# Motor.net
KiCad netlist of a schematic drawn in Altium Designer
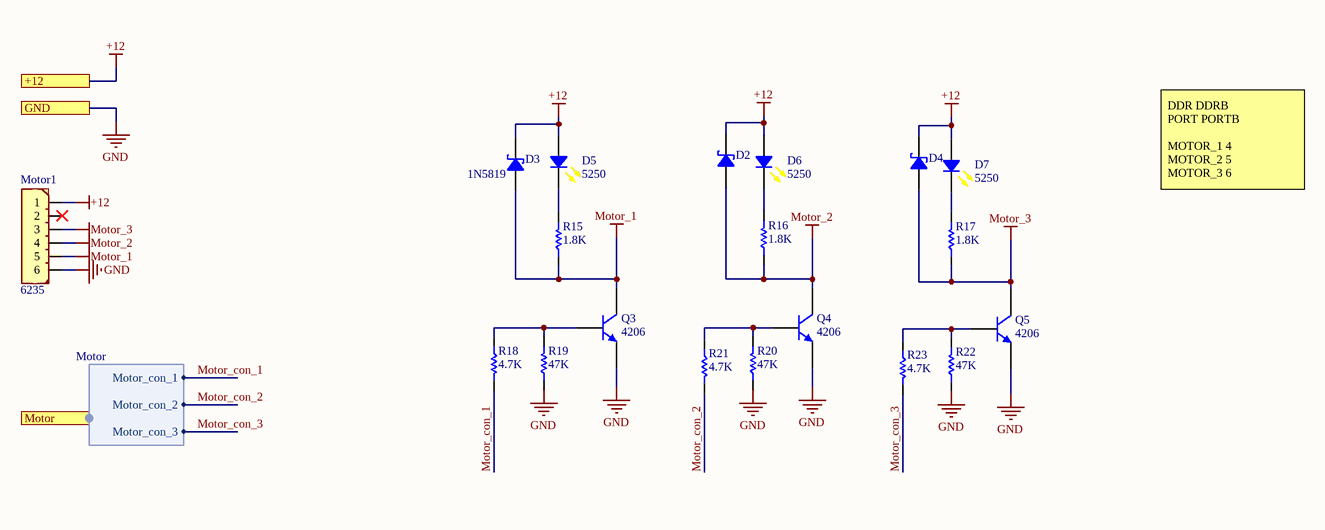
[diagram p0: Motor.SchDoc]

(export (version "E")
  (design (tool "Eeschema 10.0.6"))
  (components
    (comp (ref "D2")
      (value "1N5819")
      (footprint "430X270D")
      (description "Schottky Rectifiers")
      (fields (field (name "VALIDATION") "Valid"))
      (libsource (lib "aKaReZa") (part "Semi_Diod_Sch_1N5819_SMD"))
    )
    (comp (ref "D3")
      (value "1N5819")
      (footprint "430X270D")
      (description "Schottky Rectifiers")
      (fields (field (name "VALIDATION") "Valid"))
      (libsource (lib "aKaReZa") (part "Semi_Diod_Sch_1N5819_SMD"))
    )
    (comp (ref "D4")
      (value "1N5819")
      (footprint "430X270D")
      (description "Schottky Rectifiers")
      (fields (field (name "VALIDATION") "Valid"))
      (libsource (lib "aKaReZa") (part "Semi_Diod_Sch_1N5819_SMD"))
    )
    (comp (ref "D5")
      (value "Yellow, 1206")
      (footprint "LED 1206/3216 YELLOW")
      (description "LED")
      (fields (field (name "INFLOW") "5250") (field (name "VALIDATION") "Valid"))
      (libsource (lib "aKaReZa") (part "Semi_LED_Yellow_1206"))
    )
    (comp (ref "D6")
      (value "Yellow, 1206")
      (footprint "LED 1206/3216 YELLOW")
      (description "LED")
      (fields (field (name "INFLOW") "5250") (field (name "VALIDATION") "Valid"))
      (libsource (lib "aKaReZa") (part "Semi_LED_Yellow_1206"))
    )
    (comp (ref "D7")
      (value "Yellow, 1206")
      (footprint "LED 1206/3216 YELLOW")
      (description "LED")
      (fields (field (name "INFLOW") "5250") (field (name "VALIDATION") "Valid"))
      (libsource (lib "aKaReZa") (part "Semi_LED_Yellow_1206"))
    )
    (comp (ref "Motor1")
      (value "6'Pin")
      (footprint "645006114822")
      (description "6'Pin Power Connector")
      (fields (field (name "INFLOW") "6235") (field (name "VALIDATION") "Valid"))
      (libsource (lib "aKaReZa") (part "Con_Power_6_PC_V"))
    )
    (comp (ref "Q3")
      (value "NPN")
      (footprint "TO-220 AB")
      (description "NPN Power transistor")
      (fields (field (name "INFLOW") "4206") (field (name "VALIDATION") "NT"))
      (libsource (lib "aKaReZa") (part "Semi_BJT_TIP41C"))
    )
    (comp (ref "Q4")
      (value "NPN")
      (footprint "TO-220 AB")
      (description "NPN Power transistor")
      (fields (field (name "INFLOW") "4206") (field (name "VALIDATION") "NT"))
      (libsource (lib "aKaReZa") (part "Semi_BJT_TIP41C"))
    )
    (comp (ref "Q5")
      (value "NPN")
      (footprint "TO-220 AB")
      (description "NPN Power transistor")
      (fields (field (name "INFLOW") "4206") (field (name "VALIDATION") "NT"))
      (libsource (lib "aKaReZa") (part "Semi_BJT_TIP41C"))
    )
    (comp (ref "R15")
      (value "1.8K")
      (footprint "RES 1206 (3216X08L)")
      (description "Resistor")
      (fields (field (name "VALIDATION") "Valid"))
      (libsource (lib "aKaReZa") (part "Res_SMD_1206"))
    )
    (comp (ref "R16")
      (value "1.8K")
      (footprint "RES 1206 (3216X08L)")
      (description "Resistor")
      (fields (field (name "VALIDATION") "Valid"))
      (libsource (lib "aKaReZa") (part "Res_SMD_1206"))
    )
    (comp (ref "R17")
      (value "1.8K")
      (footprint "RES 1206 (3216X08L)")
      (description "Resistor")
      (fields (field (name "VALIDATION") "Valid"))
      (libsource (lib "aKaReZa") (part "Res_SMD_1206"))
    )
    (comp (ref "R18")
      (value "4.7K")
      (footprint "RES 1206 (3216X08L)")
      (description "Resistor")
      (fields (field (name "VALIDATION") "Valid"))
      (libsource (lib "aKaReZa") (part "Res_SMD_1206"))
    )
    (comp (ref "R19")
      (value "47K")
      (footprint "RES 1206 (3216X08L)")
      (description "Resistor")
      (fields (field (name "VALIDATION") "Valid"))
      (libsource (lib "aKaReZa") (part "Res_SMD_1206"))
    )
    (comp (ref "R20")
      (value "47K")
      (footprint "RES 1206 (3216X08L)")
      (description "Resistor")
      (fields (field (name "VALIDATION") "Valid"))
      (libsource (lib "aKaReZa") (part "Res_SMD_1206"))
    )
    (comp (ref "R21")
      (value "4.7K")
      (footprint "RES 1206 (3216X08L)")
      (description "Resistor")
      (fields (field (name "VALIDATION") "Valid"))
      (libsource (lib "aKaReZa") (part "Res_SMD_1206"))
    )
    (comp (ref "R22")
      (value "47K")
      (footprint "RES 1206 (3216X08L)")
      (description "Resistor")
      (fields (field (name "VALIDATION") "Valid"))
      (libsource (lib "aKaReZa") (part "Res_SMD_1206"))
    )
    (comp (ref "R23")
      (value "4.7K")
      (footprint "RES 1206 (3216X08L)")
      (description "Resistor")
      (fields (field (name "VALIDATION") "Valid"))
      (libsource (lib "aKaReZa") (part "Res_SMD_1206"))
    )
  )
  (nets
    (net (code "2") (name "+12") (class "Default")
      (node (ref "D2") (pin "2") (pinfunction "2_2") (pintype "passive"))
      (node (ref "D3") (pin "2") (pinfunction "2_2") (pintype "passive"))
      (node (ref "D4") (pin "2") (pinfunction "2_2") (pintype "passive"))
      (node (ref "D5") (pin "1") (pinfunction "1_1") (pintype "passive"))
      (node (ref "D6") (pin "1") (pinfunction "1_1") (pintype "passive"))
      (node (ref "D7") (pin "1") (pinfunction "1_1") (pintype "passive"))
      (node (ref "Motor1") (pin "1") (pinfunction "1_1") (pintype "passive"))
    )
    (net (code "4") (name "/Motor_con_1") (class "Default")
      (node (ref "R18") (pin "2") (pinfunction "2_2") (pintype "passive"))
    )
    (net (code "5") (name "/Motor_con_2") (class "Default")
      (node (ref "R21") (pin "2") (pinfunction "2_2") (pintype "passive"))
    )
    (net (code "6") (name "/Motor_con_3") (class "Default")
      (node (ref "R23") (pin "2") (pinfunction "2_2") (pintype "passive"))
    )
    (net (code "8") (name "GND") (class "Default")
      (node (ref "Motor1") (pin "6") (pinfunction "6_6") (pintype "passive"))
      (node (ref "Q3") (pin "3") (pinfunction "E_3") (pintype "passive"))
      (node (ref "Q4") (pin "3") (pinfunction "E_3") (pintype "passive"))
      (node (ref "Q5") (pin "3") (pinfunction "E_3") (pintype "passive"))
      (node (ref "R19") (pin "1") (pinfunction "1_1") (pintype "passive"))
      (node (ref "R20") (pin "1") (pinfunction "1_1") (pintype "passive"))
      (node (ref "R22") (pin "1") (pinfunction "1_1") (pintype "passive"))
    )
    (net (code "9") (name "Motor_1") (class "Default")
      (node (ref "D3") (pin "1") (pinfunction "1_1") (pintype "passive"))
      (node (ref "Motor1") (pin "5") (pinfunction "5_5") (pintype "passive"))
      (node (ref "Q3") (pin "2") (pinfunction "C_2") (pintype "passive"))
      (node (ref "R15") (pin "1") (pinfunction "1_1") (pintype "passive"))
    )
    (net (code "10") (name "Motor_2") (class "Default")
      (node (ref "D2") (pin "1") (pinfunction "1_1") (pintype "passive"))
      (node (ref "Motor1") (pin "4") (pinfunction "4_4") (pintype "passive"))
      (node (ref "Q4") (pin "2") (pinfunction "C_2") (pintype "passive"))
      (node (ref "R16") (pin "1") (pinfunction "1_1") (pintype "passive"))
    )
    (net (code "11") (name "Motor_3") (class "Default")
      (node (ref "D4") (pin "1") (pinfunction "1_1") (pintype "passive"))
      (node (ref "Motor1") (pin "3") (pinfunction "3_3") (pintype "passive"))
      (node (ref "Q5") (pin "2") (pinfunction "C_2") (pintype "passive"))
      (node (ref "R17") (pin "1") (pinfunction "1_1") (pintype "passive"))
    )
    (net (code "12") (name "Net-(D5-Pad2)") (class "Default")
      (node (ref "D5") (pin "2") (pinfunction "2_2") (pintype "passive"))
      (node (ref "R15") (pin "2") (pinfunction "2_2") (pintype "passive"))
    )
    (net (code "13") (name "Net-(D6-Pad2)") (class "Default")
      (node (ref "D6") (pin "2") (pinfunction "2_2") (pintype "passive"))
      (node (ref "R16") (pin "2") (pinfunction "2_2") (pintype "passive"))
    )
    (net (code "14") (name "Net-(D7-Pad2)") (class "Default")
      (node (ref "D7") (pin "2") (pinfunction "2_2") (pintype "passive"))
      (node (ref "R17") (pin "2") (pinfunction "2_2") (pintype "passive"))
    )
    (net (code "15") (name "Net-(Q3-B)") (class "Default")
      (node (ref "Q3") (pin "1") (pinfunction "B_1") (pintype "passive"))
      (node (ref "R18") (pin "1") (pinfunction "1_1") (pintype "passive"))
      (node (ref "R19") (pin "2") (pinfunction "2_2") (pintype "passive"))
    )
    (net (code "16") (name "Net-(Q4-B)") (class "Default")
      (node (ref "Q4") (pin "1") (pinfunction "B_1") (pintype "passive"))
      (node (ref "R20") (pin "2") (pinfunction "2_2") (pintype "passive"))
      (node (ref "R21") (pin "1") (pinfunction "1_1") (pintype "passive"))
    )
    (net (code "17") (name "Net-(Q5-B)") (class "Default")
      (node (ref "Q5") (pin "1") (pinfunction "B_1") (pintype "passive"))
      (node (ref "R22") (pin "2") (pinfunction "2_2") (pintype "passive"))
      (node (ref "R23") (pin "1") (pinfunction "1_1") (pintype "passive"))
    )
    (net (code "18") (name "unconnected-(Motor1-Pad2)") (class "Default")
      (node (ref "Motor1") (pin "2") (pinfunction "2_2") (pintype "passive+no_connect"))
    )
  )
)
